# Power_Regulation.net
KiCad netlist of a schematic drawn in Altium Designer
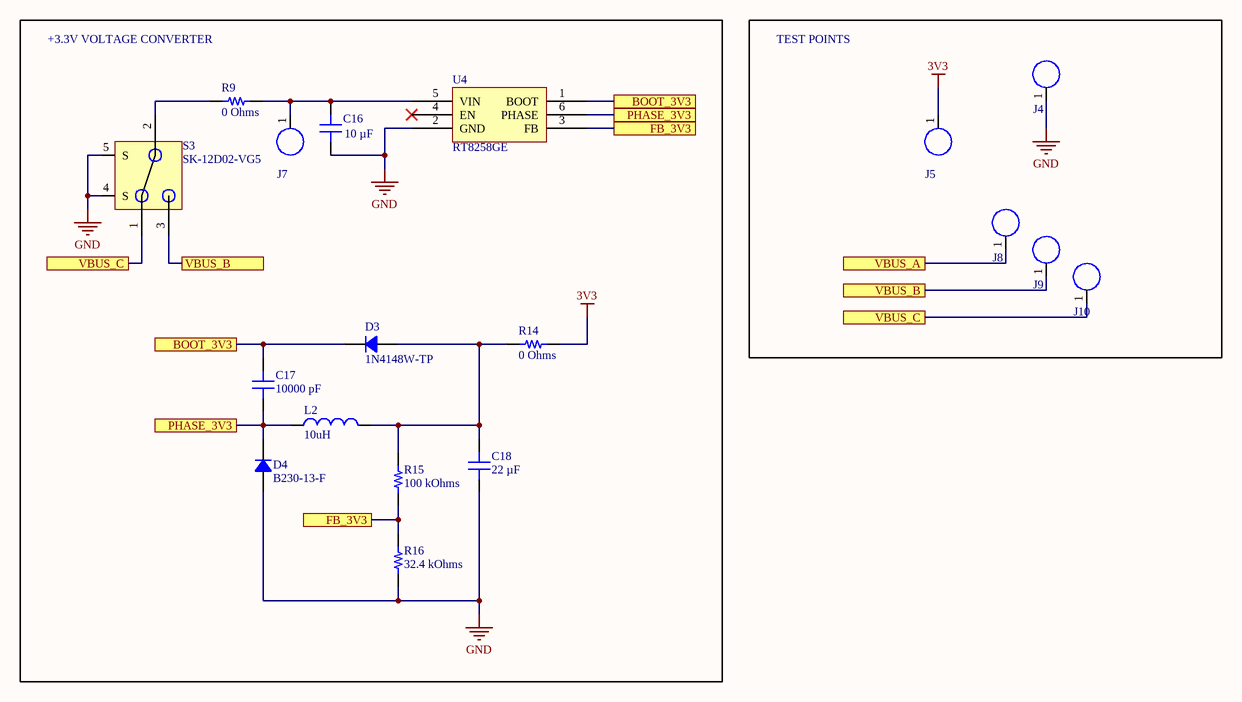
[diagram p0: Power_Regulation.SchDoc]

(export (version "E")
  (design (tool "Eeschema 10.0.6"))
  (components
    (comp (ref "C16")
      (value "10 µF")
      (footprint "CAP 1206_3216 - 0.8MM")
      (description "CAP CER 10UF 25V X7R 1206")
      (fields
        (field (name "PART NUMBER") "GRM31CR71E106MA12K")
        (field (name "MANUFACTURER") "Murata Electronics")
      )
      (libsource (lib "Celestial Altium Library - altium_library") (part "Capacitor"))
    )
    (comp (ref "C17")
      (value "10000 pF")
      (footprint "CAP 0402_1005")
      (description "CAP CER 10000PF 10V X7R 0402")
      (fields
        (field (name "PART NUMBER") "VJ0402Y103JXQCW1BC")
        (field (name "MANUFACTURER") "Vishay Vitramon")
      )
      (libsource (lib "Celestial Altium Library - altium_library") (part "Capacitor"))
    )
    (comp (ref "C18")
      (value "22 µF")
      (footprint "CAP 1206_3216 - 0.8MM")
      (description "CAP CER 22UF 6.3V X7R 1206")
      (fields
        (field (name "PART NUMBER") "GCM31CR70J226KE23L")
        (field (name "MANUFACTURER") "Murata Electronics")
      )
      (libsource (lib "Celestial Altium Library - altium_library") (part "Capacitor"))
    )
    (comp (ref "D3")
      (value "1N4148W-TP")
      (footprint "SOD-123")
      (description "DIODE GEN PURP 100V 150MA SOD123")
      (fields (field (name "MANUFACTURER") "Micro Commercial Co"))
      (libsource (lib "Celestial Altium Library - altium_library") (part "Diode"))
    )
    (comp (ref "D4")
      (value "B230-13-F")
      (footprint "DO214AA SMB")
      (description "DIODE SCHOTTKY 30V 2A SMB")
      (fields (field (name "MANUFACTURER") "Diodes Incorporated"))
      (libsource (lib "Celestial Altium Library - altium_library") (part "Diode"))
    )
    (comp (ref "J4")
      (value "Large Board Solder Point")
      (footprint "Large Solder Point")
      (libsource (lib "Schlib2") (part "Large Board Solder Point"))
    )
    (comp (ref "J5")
      (value "Large Board Solder Point")
      (footprint "Large Solder Point")
      (libsource (lib "Schlib2") (part "Large Board Solder Point"))
    )
    (comp (ref "J7")
      (value "Large Board Solder Point")
      (footprint "Large Solder Point")
      (libsource (lib "Schlib2") (part "Large Board Solder Point"))
    )
    (comp (ref "J8")
      (value "Large Board Solder Point")
      (footprint "Large Solder Point")
      (libsource (lib "Schlib2") (part "Large Board Solder Point"))
    )
    (comp (ref "J9")
      (value "Large Board Solder Point")
      (footprint "Large Solder Point")
      (libsource (lib "Schlib2") (part "Large Board Solder Point"))
    )
    (comp (ref "J10")
      (value "Large Board Solder Point")
      (footprint "Large Solder Point")
      (libsource (lib "Schlib2") (part "Large Board Solder Point"))
    )
    (comp (ref "L2")
      (value "10uH")
      (footprint "0630CDMCCDS-100MC")
      (description "4A 10uH ±20% 67mΩ SMD,7x6.6x2.8mm Power Inductors ROHS")
      (libsource (lib "Schlib2") (part "0630CDMCCDS-100MC"))
    )
    (comp (ref "R9")
      (value "0 Ohms")
      (footprint "RES 1210_3225")
      (description "RES 0 OHM JUMPER 1/2W 1210")
      (fields (field (name "PART NUMBER") "RC1210JR-070RL") (field (name "MANUFACTURER") "Yageo"))
      (libsource (lib "Celestial Altium Library - altium_library") (part "Resistor"))
    )
    (comp (ref "R14")
      (value "0 Ohms")
      (footprint "RES 1210_3225")
      (description "RES 0 OHM JUMPER 1/2W 1210")
      (fields (field (name "PART NUMBER") "RC1210JR-070RL") (field (name "MANUFACTURER") "Yageo"))
      (libsource (lib "Celestial Altium Library - altium_library") (part "Resistor"))
    )
    (comp (ref "R15")
      (value "100 kOhms")
      (footprint "RES 0402_1005")
      (description "RES 100K OHM 0.1% 1/10W 0402")
      (fields
        (field (name "PART NUMBER") "RP73PF1E100KBTD")
        (field (name "MANUFACTURER") "TE Connectivity Passive Product")
      )
      (libsource (lib "Celestial Altium Library - altium_library") (part "Resistor"))
    )
    (comp (ref "R16")
      (value "32.4 kOhms")
      (footprint "RES 0402_1005")
      (description "RES SMD 32.4KOHM 0.1% 1/16W 0402")
      (fields
        (field (name "PART NUMBER") "CPF0402B32K4E1")
        (field (name "MANUFACTURER") "TE Connectivity Passive Product")
      )
      (libsource (lib "Celestial Altium Library - altium_library") (part "Resistor"))
    )
    (comp (ref "S3")
      (value "SK-12D02-VG5")
      (footprint "SK-12D02-VG5")
      (description "Lying SPDT 9.5mm PCPin 5000 Rectangular columnar -25℃~+70℃ Plugin Slide Switches ROHS SP#C136722")
      (libsource (lib "Power_Measurement") (part "SK-12D02-VG5"))
    )
    (comp (ref "U4")
      (value "RT8258GE")
      (footprint "SOT100P279X130-6N")
      (description "RICHTEK 1.2A, 24V, 700kHz Step-Down Converter SOT23-6")
      (libsource (lib "Schlib2") (part "RT8258GE"))
    )
  )
  (nets
    (net (code "1") (name "/BOOT_3V3") (class "Default")
      (node (ref "C17") (pin "2") (pinfunction "2_2") (pintype "passive"))
      (node (ref "D3") (pin "2") (pinfunction "2_2") (pintype "passive"))
      (node (ref "U4") (pin "1") (pinfunction "BOOT_1") (pintype "passive"))
    )
    (net (code "2") (name "/FB_3V3") (class "Default")
      (node (ref "R15") (pin "1") (pinfunction "1_1") (pintype "passive"))
      (node (ref "R16") (pin "2") (pinfunction "2_2") (pintype "passive"))
      (node (ref "U4") (pin "3") (pinfunction "FB_3") (pintype "passive"))
    )
    (net (code "3") (name "/PHASE_3V3") (class "Default")
      (node (ref "C17") (pin "1") (pinfunction "1_1") (pintype "passive"))
      (node (ref "D4") (pin "2") (pinfunction "2_2") (pintype "passive"))
      (node (ref "L2") (pin "1") (pinfunction "1_1") (pintype "passive"))
      (node (ref "U4") (pin "6") (pinfunction "PHASE_6") (pintype "passive"))
    )
    (net (code "4") (name "/VBUS_A") (class "Default") (node (ref "J8") (pin "1") (pintype "passive")))
    (net (code "5") (name "/VBUS_B") (class "Default")
      (node (ref "J9") (pin "1") (pintype "passive"))
      (node (ref "S3") (pin "3") (pinfunction "3_3") (pintype "passive"))
    )
    (net (code "6") (name "/VBUS_C") (class "Default")
      (node (ref "J10") (pin "1") (pintype "passive"))
      (node (ref "S3") (pin "1") (pinfunction "1_1") (pintype "passive"))
    )
    (net (code "7") (name "3V3") (class "Default")
      (node (ref "J5") (pin "1") (pintype "passive"))
      (node (ref "R14") (pin "2") (pinfunction "2_2") (pintype "passive"))
    )
    (net (code "8") (name "GND") (class "Default")
      (node (ref "C16") (pin "1") (pinfunction "1_1") (pintype "passive"))
      (node (ref "C18") (pin "2") (pinfunction "2_2") (pintype "passive"))
      (node (ref "D4") (pin "1") (pinfunction "1_1") (pintype "passive"))
      (node (ref "J4") (pin "1") (pintype "passive"))
      (node (ref "R16") (pin "1") (pinfunction "1_1") (pintype "passive"))
      (node (ref "S3") (pin "4") (pinfunction "S_4") (pintype "passive"))
      (node (ref "S3") (pin "5") (pinfunction "S_5") (pintype "passive"))
      (node (ref "U4") (pin "2") (pinfunction "GND_2") (pintype "passive"))
    )
    (net (code "9") (name "Net-(C18-Pad1)") (class "Default")
      (node (ref "C18") (pin "1") (pinfunction "1_1") (pintype "passive"))
      (node (ref "D3") (pin "1") (pinfunction "1_1") (pintype "passive"))
      (node (ref "L2") (pin "2") (pinfunction "2_2") (pintype "passive"))
      (node (ref "R14") (pin "1") (pinfunction "1_1") (pintype "passive"))
      (node (ref "R15") (pin "2") (pinfunction "2_2") (pintype "passive"))
    )
    (net (code "10") (name "Net-(S3-C)") (class "Default")
      (node (ref "R9") (pin "1") (pinfunction "1_1") (pintype "passive"))
      (node (ref "S3") (pin "2") (pinfunction "C_2") (pintype "passive"))
    )
    (net (code "11") (name "Net-(U4-VIN)") (class "Default")
      (node (ref "C16") (pin "2") (pinfunction "2_2") (pintype "passive"))
      (node (ref "J7") (pin "1") (pintype "passive"))
      (node (ref "R9") (pin "2") (pinfunction "2_2") (pintype "passive"))
      (node (ref "U4") (pin "5") (pinfunction "VIN_5") (pintype "passive"))
    )
    (net (code "12") (name "unconnected-(U4-EN-Pad4)") (class "Default")
      (node (ref "U4") (pin "4") (pinfunction "EN_4") (pintype "passive+no_connect"))
    )
  )
)
